# LB-word-gpioExpanders.net
KiCad netlist of a schematic drawn in Altium Designer
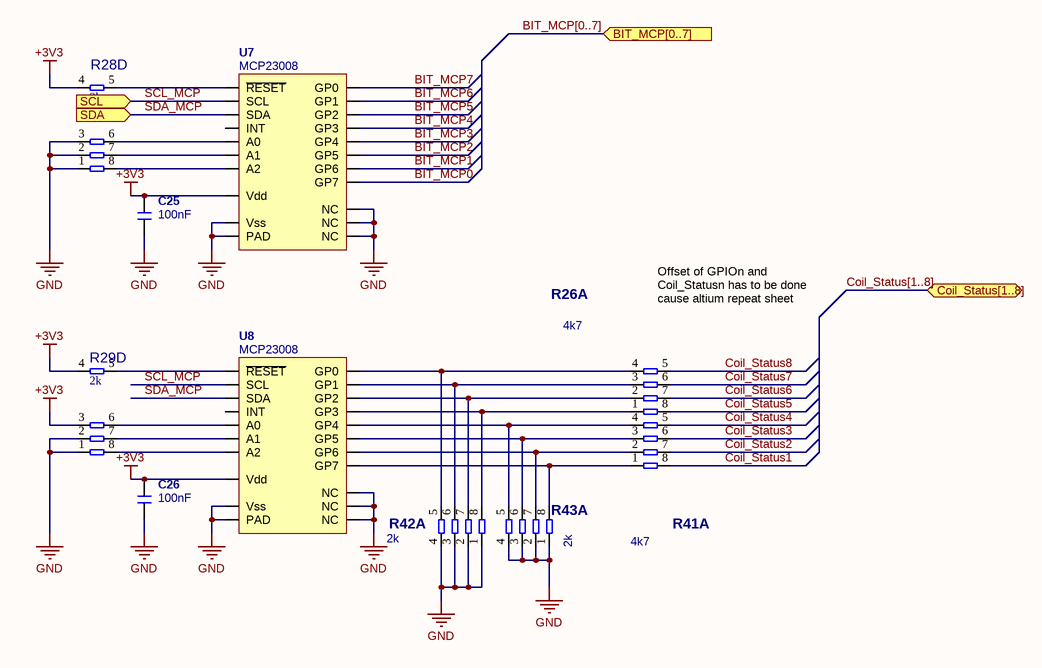
[diagram p0: LB-word-gpioExpanders.SchDoc]

(export (version "E")
  (design (tool "Eeschema 10.0.6"))
  (components
    (comp (ref "C25")
      (value "100nF")
      (footprint "C0603_N")
      (description "Capacitor MLCC")
      (fields
        (field (name "MANUFACTURER") "Yageo")
        (field (name "MANUFACTURER PART NUMBER") "CC0603KRX7R9BB104")
      )
      (libsource (lib "wes") (part "Capacitor"))
    )
    (comp (ref "C26")
      (value "100nF")
      (footprint "C0603_N")
      (description "Capacitor MLCC")
      (fields
        (field (name "MANUFACTURER") "Yageo")
        (field (name "MANUFACTURER PART NUMBER") "CC0603KRX7R9BB104")
      )
      (libsource (lib "wes") (part "Capacitor"))
    )
    (comp (ref "R26")
      (value "4k7")
      (footprint "YC164")
      (fields (field (name "Comment") "; 4k7"))
      (libsource (lib "wes") (part "Resistor Array - 4P"))
    )
    (comp (ref "R28")
      (value "; 2k")
      (footprint "YC164")
      (fields (field (name "Comment") "; 2k"))
      (libsource (lib "wes") (part "Resistor Array - 4P"))
    )
    (comp (ref "R29")
      (value "; 2k")
      (footprint "YC164")
      (fields (field (name "Comment") "; 2k"))
      (libsource (lib "wes") (part "Resistor Array - 4P"))
    )
    (comp (ref "R41")
      (value "4k7")
      (footprint "YC164")
      (fields (field (name "Comment") "; 4k7"))
      (libsource (lib "wes") (part "Resistor Array - 4P"))
    )
    (comp (ref "R42")
      (value "2k")
      (footprint "YC164")
      (fields (field (name "Comment") "; 2k"))
      (libsource (lib "wes") (part "Resistor Array - 4P"))
    )
    (comp (ref "R43")
      (value "2k")
      (footprint "YC164")
      (fields (field (name "Comment") "; 2k"))
      (libsource (lib "wes") (part "Resistor Array - 4P"))
    )
    (comp (ref "U7")
      (value "MCP23008")
      (footprint "QFN20")
      (description "I2C Port Expander")
      (libsource (lib "wes") (part "MCP23008"))
    )
    (comp (ref "U8")
      (value "MCP23008")
      (footprint "QFN20")
      (description "I2C Port Expander")
      (libsource (lib "wes") (part "MCP23008"))
    )
  )
  (nets
    (net (code "1") (name "+3V3") (class "Default")
      (node (ref "C25") (pin "1") (pintype "passive"))
      (node (ref "C26") (pin "1") (pintype "passive"))
      (node (ref "R28") (pin "4") (pinfunction "4_4") (pintype "passive"))
      (node (ref "R29") (pin "3") (pinfunction "3_3") (pintype "passive"))
      (node (ref "R29") (pin "4") (pinfunction "4_4") (pintype "passive"))
      (node (ref "U7") (pin "18") (pinfunction "Vdd_18") (pintype "passive"))
      (node (ref "U8") (pin "18") (pinfunction "Vdd_18") (pintype "passive"))
    )
    (net (code "2") (name "/BIT_MCP0") (class "Default")
      (node (ref "U7") (pin "16") (pinfunction "GP7_16") (pintype "passive"))
    )
    (net (code "3") (name "/BIT_MCP1") (class "Default")
      (node (ref "U7") (pin "15") (pinfunction "GP6_15") (pintype "passive"))
    )
    (net (code "4") (name "/BIT_MCP2") (class "Default")
      (node (ref "U7") (pin "14") (pinfunction "GP5_14") (pintype "passive"))
    )
    (net (code "5") (name "/BIT_MCP3") (class "Default")
      (node (ref "U7") (pin "13") (pinfunction "GP4_13") (pintype "passive"))
    )
    (net (code "6") (name "/BIT_MCP4") (class "Default")
      (node (ref "U7") (pin "12") (pinfunction "GP3_12") (pintype "passive"))
    )
    (net (code "7") (name "/BIT_MCP5") (class "Default")
      (node (ref "U7") (pin "11") (pinfunction "GP2_11") (pintype "passive"))
    )
    (net (code "8") (name "/BIT_MCP6") (class "Default")
      (node (ref "U7") (pin "10") (pinfunction "GP1_10") (pintype "passive"))
    )
    (net (code "9") (name "/BIT_MCP7") (class "Default")
      (node (ref "U7") (pin "9") (pinfunction "GP0_9") (pintype "passive"))
    )
    (net (code "11") (name "/Coil_Status1") (class "Default")
      (node (ref "R41") (pin "8") (pinfunction "8_8") (pintype "passive"))
    )
    (net (code "12") (name "/Coil_Status2") (class "Default")
      (node (ref "R41") (pin "7") (pinfunction "7_7") (pintype "passive"))
    )
    (net (code "13") (name "/Coil_Status3") (class "Default")
      (node (ref "R41") (pin "6") (pinfunction "6_6") (pintype "passive"))
    )
    (net (code "14") (name "/Coil_Status4") (class "Default")
      (node (ref "R41") (pin "5") (pinfunction "5_5") (pintype "passive"))
    )
    (net (code "15") (name "/Coil_Status5") (class "Default")
      (node (ref "R26") (pin "8") (pinfunction "8_8") (pintype "passive"))
    )
    (net (code "16") (name "/Coil_Status6") (class "Default")
      (node (ref "R26") (pin "7") (pinfunction "7_7") (pintype "passive"))
    )
    (net (code "17") (name "/Coil_Status7") (class "Default")
      (node (ref "R26") (pin "6") (pinfunction "6_6") (pintype "passive"))
    )
    (net (code "18") (name "/Coil_Status8") (class "Default")
      (node (ref "R26") (pin "5") (pinfunction "5_5") (pintype "passive"))
    )
    (net (code "20") (name "/SCL_MCP") (class "Default")
      (node (ref "U7") (pin "19") (pinfunction "SCL_19") (pintype "passive"))
      (node (ref "U8") (pin "19") (pinfunction "SCL_19") (pintype "passive"))
    )
    (net (code "21") (name "/SDA_MCP") (class "Default")
      (node (ref "U7") (pin "20") (pinfunction "SDA_20") (pintype "passive"))
      (node (ref "U8") (pin "20") (pinfunction "SDA_20") (pintype "passive"))
    )
    (net (code "22") (name "GND") (class "Default")
      (node (ref "C25") (pin "2") (pintype "passive"))
      (node (ref "C26") (pin "2") (pintype "passive"))
      (node (ref "R28") (pin "1") (pinfunction "1_1") (pintype "passive"))
      (node (ref "R28") (pin "2") (pinfunction "2_2") (pintype "passive"))
      (node (ref "R28") (pin "3") (pinfunction "3_3") (pintype "passive"))
      (node (ref "R29") (pin "1") (pinfunction "1_1") (pintype "passive"))
      (node (ref "R29") (pin "2") (pinfunction "2_2") (pintype "passive"))
      (node (ref "R42") (pin "1") (pinfunction "1_1") (pintype "passive"))
      (node (ref "R42") (pin "2") (pinfunction "2_2") (pintype "passive"))
      (node (ref "R42") (pin "3") (pinfunction "3_3") (pintype "passive"))
      (node (ref "R42") (pin "4") (pinfunction "4_4") (pintype "passive"))
      (node (ref "R43") (pin "1") (pinfunction "1_1") (pintype "passive"))
      (node (ref "R43") (pin "2") (pinfunction "2_2") (pintype "passive"))
      (node (ref "R43") (pin "3") (pinfunction "3_3") (pintype "passive"))
      (node (ref "R43") (pin "4") (pinfunction "4_4") (pintype "passive"))
      (node (ref "U7") (pin "17") (pinfunction "Vss_17") (pintype "passive"))
      (node (ref "U7") (pin "5") (pinfunction "NC_5") (pintype "passive"))
      (node (ref "U7") (pin "6") (pinfunction "NC_6") (pintype "passive"))
      (node (ref "U7") (pin "8") (pinfunction "NC_8") (pintype "passive"))
      (node (ref "U7") (pin "PAD") (pinfunction "PAD_PAD") (pintype "passive"))
      (node (ref "U8") (pin "17") (pinfunction "Vss_17") (pintype "passive"))
      (node (ref "U8") (pin "5") (pinfunction "NC_5") (pintype "passive"))
      (node (ref "U8") (pin "6") (pinfunction "NC_6") (pintype "passive"))
      (node (ref "U8") (pin "8") (pinfunction "NC_8") (pintype "passive"))
      (node (ref "U8") (pin "PAD") (pinfunction "PAD_PAD") (pintype "passive"))
    )
    (net (code "23") (name "Net-(U7-A0)") (class "Default")
      (node (ref "R28") (pin "6") (pinfunction "6_6") (pintype "passive"))
      (node (ref "U7") (pin "3") (pinfunction "A0_3") (pintype "passive"))
    )
    (net (code "24") (name "Net-(U7-A1)") (class "Default")
      (node (ref "R28") (pin "7") (pinfunction "7_7") (pintype "passive"))
      (node (ref "U7") (pin "2") (pinfunction "A1_2") (pintype "passive"))
    )
    (net (code "25") (name "Net-(U7-A2)") (class "Default")
      (node (ref "R28") (pin "8") (pinfunction "8_8") (pintype "passive"))
      (node (ref "U7") (pin "1") (pinfunction "A2_1") (pintype "passive"))
    )
    (net (code "26") (name "Net-(U7-~{RESET})") (class "Default")
      (node (ref "R28") (pin "5") (pinfunction "5_5") (pintype "passive"))
      (node (ref "U7") (pin "4") (pinfunction "~{RESET}_4") (pintype "passive"))
    )
    (net (code "27") (name "Net-(U8-A0)") (class "Default")
      (node (ref "R29") (pin "6") (pinfunction "6_6") (pintype "passive"))
      (node (ref "U8") (pin "3") (pinfunction "A0_3") (pintype "passive"))
    )
    (net (code "28") (name "Net-(U8-A1)") (class "Default")
      (node (ref "R29") (pin "7") (pinfunction "7_7") (pintype "passive"))
      (node (ref "U8") (pin "2") (pinfunction "A1_2") (pintype "passive"))
    )
    (net (code "29") (name "Net-(U8-A2)") (class "Default")
      (node (ref "R29") (pin "8") (pinfunction "8_8") (pintype "passive"))
      (node (ref "U8") (pin "1") (pinfunction "A2_1") (pintype "passive"))
    )
    (net (code "30") (name "Net-(U8-GP0)") (class "Default")
      (node (ref "R26") (pin "4") (pinfunction "4_4") (pintype "passive"))
      (node (ref "R42") (pin "5") (pinfunction "5_5") (pintype "passive"))
      (node (ref "U8") (pin "9") (pinfunction "GP0_9") (pintype "passive"))
    )
    (net (code "31") (name "Net-(U8-GP1)") (class "Default")
      (node (ref "R26") (pin "3") (pinfunction "3_3") (pintype "passive"))
      (node (ref "R42") (pin "6") (pinfunction "6_6") (pintype "passive"))
      (node (ref "U8") (pin "10") (pinfunction "GP1_10") (pintype "passive"))
    )
    (net (code "32") (name "Net-(U8-GP2)") (class "Default")
      (node (ref "R26") (pin "2") (pinfunction "2_2") (pintype "passive"))
      (node (ref "R42") (pin "7") (pinfunction "7_7") (pintype "passive"))
      (node (ref "U8") (pin "11") (pinfunction "GP2_11") (pintype "passive"))
    )
    (net (code "33") (name "Net-(U8-GP3)") (class "Default")
      (node (ref "R26") (pin "1") (pinfunction "1_1") (pintype "passive"))
      (node (ref "R42") (pin "8") (pinfunction "8_8") (pintype "passive"))
      (node (ref "U8") (pin "12") (pinfunction "GP3_12") (pintype "passive"))
    )
    (net (code "34") (name "Net-(U8-GP4)") (class "Default")
      (node (ref "R41") (pin "4") (pinfunction "4_4") (pintype "passive"))
      (node (ref "R43") (pin "5") (pinfunction "5_5") (pintype "passive"))
      (node (ref "U8") (pin "13") (pinfunction "GP4_13") (pintype "passive"))
    )
    (net (code "35") (name "Net-(U8-GP5)") (class "Default")
      (node (ref "R41") (pin "3") (pinfunction "3_3") (pintype "passive"))
      (node (ref "R43") (pin "6") (pinfunction "6_6") (pintype "passive"))
      (node (ref "U8") (pin "14") (pinfunction "GP5_14") (pintype "passive"))
    )
    (net (code "36") (name "Net-(U8-GP6)") (class "Default")
      (node (ref "R41") (pin "2") (pinfunction "2_2") (pintype "passive"))
      (node (ref "R43") (pin "7") (pinfunction "7_7") (pintype "passive"))
      (node (ref "U8") (pin "15") (pinfunction "GP6_15") (pintype "passive"))
    )
    (net (code "37") (name "Net-(U8-GP7)") (class "Default")
      (node (ref "R41") (pin "1") (pinfunction "1_1") (pintype "passive"))
      (node (ref "R43") (pin "8") (pinfunction "8_8") (pintype "passive"))
      (node (ref "U8") (pin "16") (pinfunction "GP7_16") (pintype "passive"))
    )
    (net (code "38") (name "Net-(U8-~{RESET})") (class "Default")
      (node (ref "R29") (pin "5") (pinfunction "5_5") (pintype "passive"))
      (node (ref "U8") (pin "4") (pinfunction "~{RESET}_4") (pintype "passive"))
    )
    (net (code "39") (name "unconnected-(U7-INT-Pad7)") (class "Default")
      (node (ref "U7") (pin "7") (pinfunction "INT_7") (pintype "passive"))
    )
    (net (code "40") (name "unconnected-(U8-INT-Pad7)") (class "Default")
      (node (ref "U8") (pin "7") (pinfunction "INT_7") (pintype "passive"))
    )
  )
)
